# DCDCDC.net
KiCad netlist of a schematic drawn in EAGLE
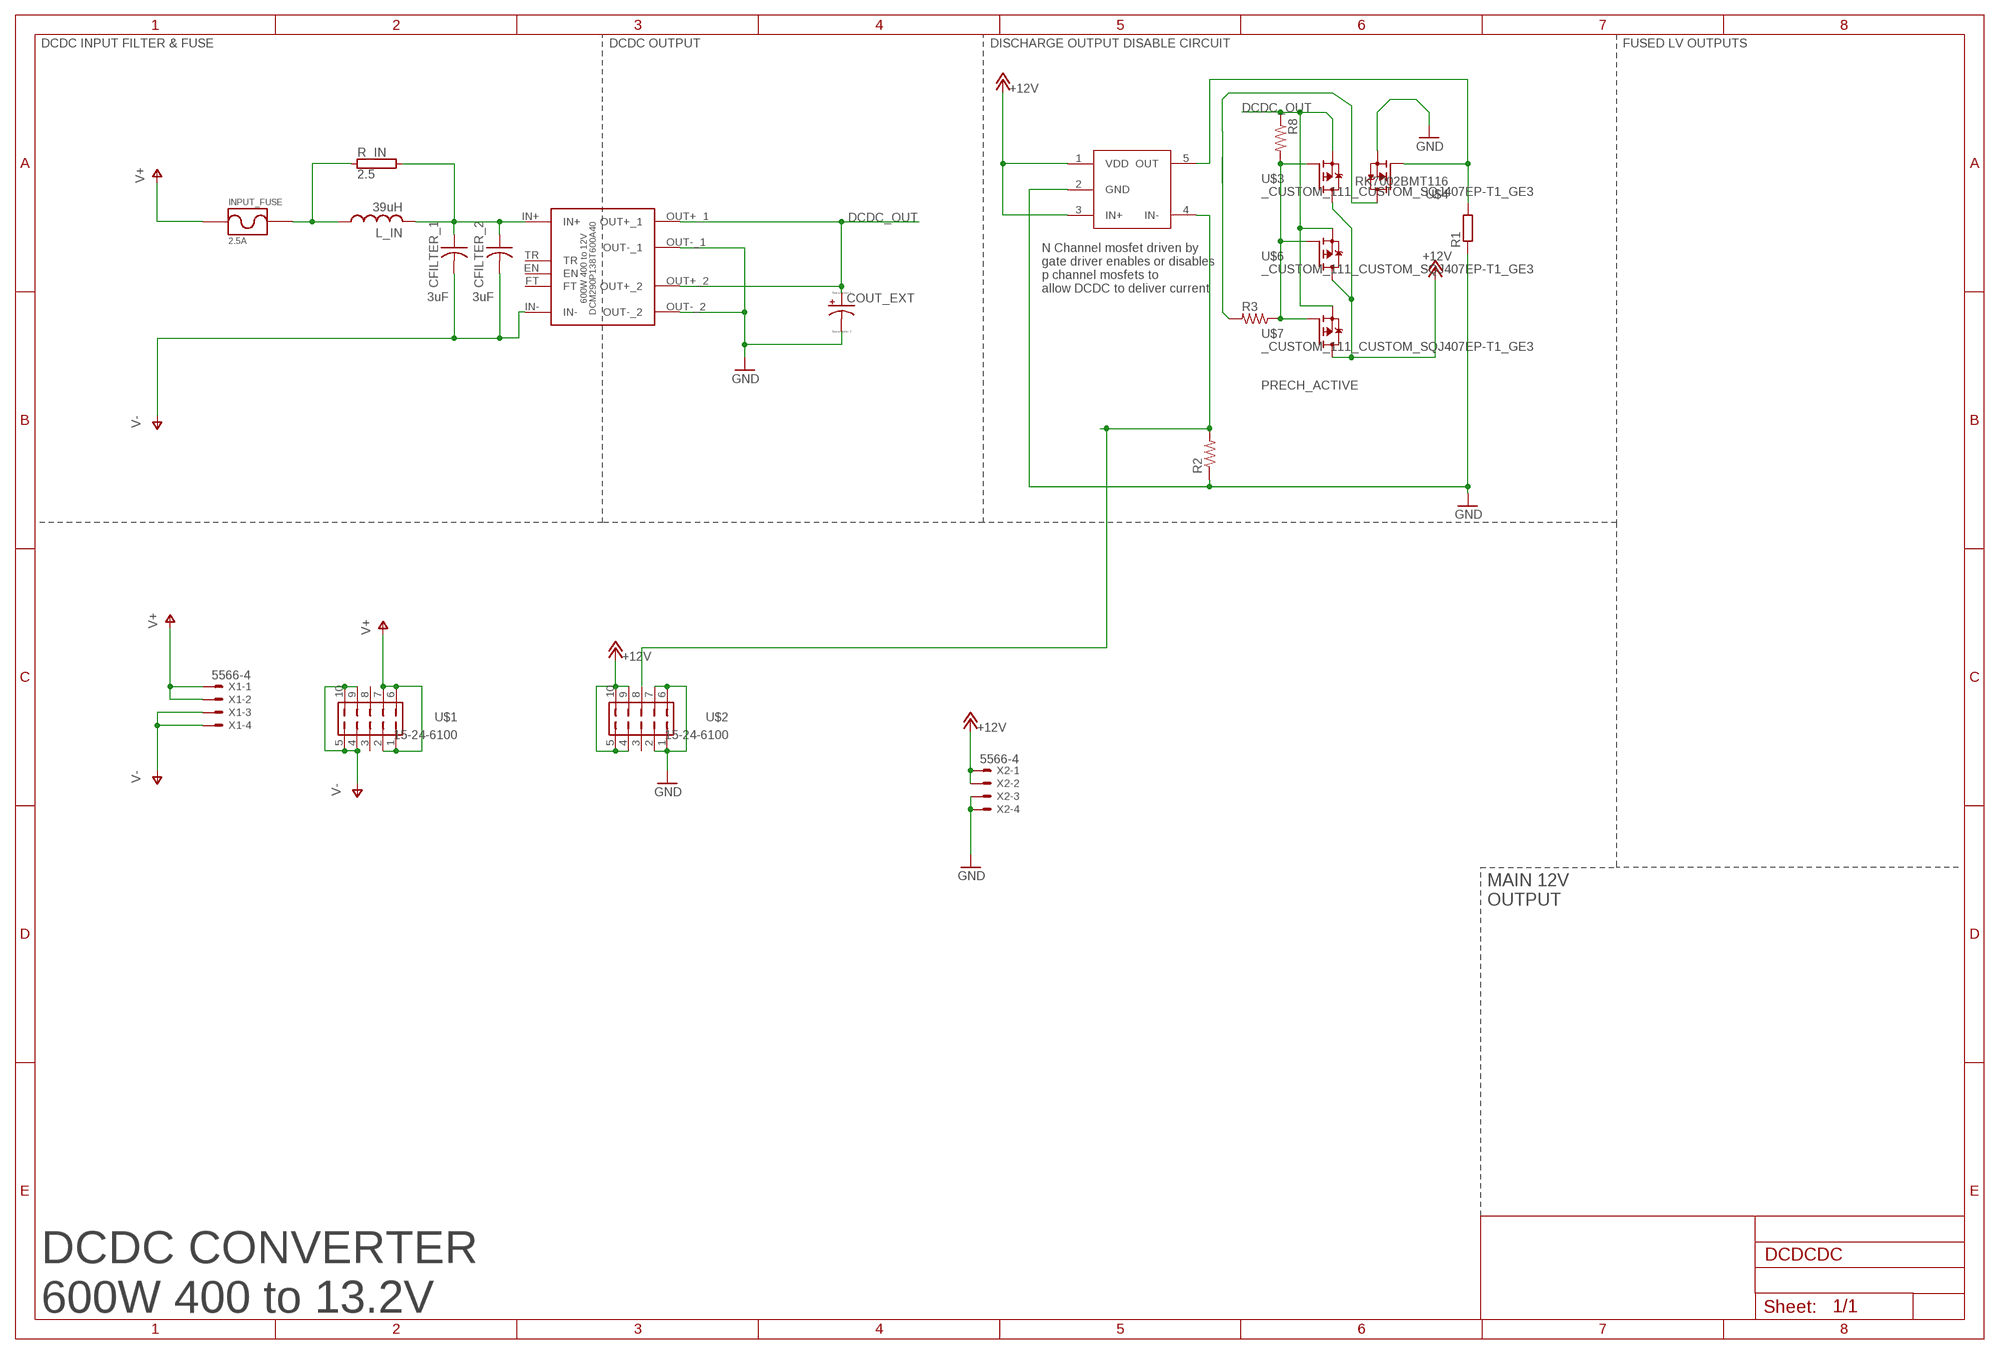
[diagram p0: schematic, sheet 1]

(export (version "E")
  (design (tool "Eeschema 10.0.6"))
  (components
    (comp (ref "CFILTER_1")
      (value "3uF")
      (footprint "eagle-import:CERALINK_FA3")
      (libsource (lib "eagle-import") (part "B58035U5305M062"))
    )
    (comp (ref "CFILTER_2")
      (value "3uF")
      (footprint "eagle-import:CERALINK_FA3")
      (libsource (lib "eagle-import") (part "B58035U5305M062"))
    )
    (comp (ref "COUT_EXT")
      (value "CPOL-USE7.5-16")
      (footprint "eagle-import:E7,5-16")
      (libsource (lib "eagle-import") (part "CPOL-USE7.5-16"))
    )
    (comp (ref "DCM290P138T600A40")
      (value "600W 400 to 12V")
      (footprint "eagle-import:VICOR_CHIP_HEATSINK")
      (libsource (lib "eagle-import") (part "VICOR_CHIP_WITH_HEATSINK"))
    )
    (comp (ref "INPUT_FUSE")
      (value "2.5A")
      (footprint "eagle-import:_CUSTOM_PARTS_LF_885")
      (libsource (lib "eagle-import") (part "_CUSTOM_PARTS_LF_885"))
    )
    (comp (ref "L_IN")
      (value "39uH")
      (footprint "eagle-import:L_1510_NONSTANDARD")
      (libsource (lib "eagle-import") (part "SRP1770TA-390M"))
    )
    (comp (ref "R1")
      (value "R-EU_R0805")
      (footprint "eagle-import:R0805")
      (libsource (lib "eagle-import") (part "R-EU_R0805"))
    )
    (comp (ref "R2")
      (value "R-US_R0805")
      (footprint "eagle-import:R0805")
      (libsource (lib "eagle-import") (part "R-US_R0805"))
    )
    (comp (ref "R3")
      (value "R-US_R0805")
      (footprint "eagle-import:R0805")
      (libsource (lib "eagle-import") (part "R-US_R0805"))
    )
    (comp (ref "R8")
      (value "R-US_R0805")
      (footprint "eagle-import:R0805")
      (libsource (lib "eagle-import") (part "R-US_R0805"))
    )
    (comp (ref "R_IN")
      (value "2.5")
      (footprint "eagle-import:TO-247-2V")
      (libsource (lib "eagle-import") (part "RMG100-V"))
    )
    (comp (ref "U$1")
      (value "15-24-6100")
      (footprint "eagle-import:15-24-6100")
      (libsource (lib "eagle-import") (part "15-24-6100"))
    )
    (comp (ref "U$2")
      (value "15-24-6100")
      (footprint "eagle-import:15-24-6100")
      (libsource (lib "eagle-import") (part "15-24-6100"))
    )
    (comp (ref "U$3")
      (value "_CUSTOM_111_CUSTOM_SQJ407EP-T1_GE3")
      (footprint "eagle-import:_CUSTOM_111_CUSTOM_TRANS_SIRA90DP-T1-GE3")
      (libsource (lib "eagle-import") (part "_CUSTOM_111_CUSTOM_SQJ407EP-T1_GE3"))
    )
    (comp (ref "U$4")
      (value "RK7002BMT116")
      (footprint "eagle-import:SOT23")
      (libsource (lib "eagle-import") (part "RK7002BMT116"))
    )
    (comp (ref "U$5")
      (value "UCC27511AQDBVRQ1")
      (footprint "eagle-import:SOT23-5L")
      (libsource (lib "eagle-import") (part "UCC27511AQDBVRQ1"))
    )
    (comp (ref "U$6")
      (value "_CUSTOM_111_CUSTOM_SQJ407EP-T1_GE3")
      (footprint "eagle-import:_CUSTOM_111_CUSTOM_TRANS_SIRA90DP-T1-GE3")
      (libsource (lib "eagle-import") (part "_CUSTOM_111_CUSTOM_SQJ407EP-T1_GE3"))
    )
    (comp (ref "U$7")
      (value "_CUSTOM_111_CUSTOM_SQJ407EP-T1_GE3")
      (footprint "eagle-import:_CUSTOM_111_CUSTOM_TRANS_SIRA90DP-T1-GE3")
      (libsource (lib "eagle-import") (part "_CUSTOM_111_CUSTOM_SQJ407EP-T1_GE3"))
    )
    (comp (ref "X1")
      (value "5566-4")
      (footprint "eagle-import:5566-4")
      (fields (field (name "MF") "MOLEX"))
      (libsource (lib "eagle-import") (part "5566-4"))
    )
    (comp (ref "X2")
      (value "5566-4")
      (footprint "eagle-import:5566-4")
      (fields (field (name "MF") "MOLEX"))
      (libsource (lib "eagle-import") (part "5566-4"))
    )
  )
  (nets
    (net (code "1") (name "+12V") (class "Default")
      (node (ref "U$2") (pin "10") (pinfunction "10_10") (pintype "passive"))
      (node (ref "U$2") (pin "4") (pinfunction "4_4") (pintype "passive"))
      (node (ref "U$2") (pin "5") (pinfunction "5_5") (pintype "passive"))
      (node (ref "U$2") (pin "9") (pinfunction "9_9") (pintype "passive"))
      (node (ref "U$3") (pin "5") (pinfunction "D_5") (pintype "passive"))
      (node (ref "U$5") (pin "1") (pinfunction "VDD_1") (pintype "bidirectional"))
      (node (ref "U$5") (pin "3") (pinfunction "IN+_3") (pintype "bidirectional"))
      (node (ref "U$6") (pin "5") (pinfunction "D_5") (pintype "passive"))
      (node (ref "U$7") (pin "5") (pinfunction "D_5") (pintype "passive"))
      (node (ref "X2") (pin "1") (pinfunction "S_1") (pintype "passive"))
      (node (ref "X2") (pin "2") (pinfunction "S_2") (pintype "passive"))
    )
    (net (code "2") (name "/DCDC_OUT") (class "Default")
      (node (ref "COUT_EXT") (pin "+") (pinfunction "+_+") (pintype "passive"))
      (node (ref "DCM290P138T600A40") (pin "OUT+_1") (pinfunction "OUT+_1_OUT+_1") (pintype "bidirectional"))
      (node (ref "DCM290P138T600A40") (pin "OUT+_2") (pinfunction "OUT+_2_OUT+_2") (pintype "bidirectional"))
      (node (ref "R8") (pin "1") (pinfunction "1_1") (pintype "passive"))
      (node (ref "U$3") (pin "1") (pinfunction "S_1") (pintype "passive"))
      (node (ref "U$3") (pin "2") (pinfunction "S_2") (pintype "passive"))
      (node (ref "U$3") (pin "3") (pinfunction "S_3") (pintype "passive"))
      (node (ref "U$6") (pin "1") (pinfunction "S_1") (pintype "passive"))
      (node (ref "U$6") (pin "2") (pinfunction "S_2") (pintype "passive"))
      (node (ref "U$6") (pin "3") (pinfunction "S_3") (pintype "passive"))
      (node (ref "U$7") (pin "1") (pinfunction "S_1") (pintype "passive"))
      (node (ref "U$7") (pin "2") (pinfunction "S_2") (pintype "passive"))
      (node (ref "U$7") (pin "3") (pinfunction "S_3") (pintype "passive"))
    )
    (net (code "3") (name "/PRECH_ACTIVE") (class "Default")
      (node (ref "R2") (pin "2") (pinfunction "2_2") (pintype "passive"))
      (node (ref "U$2") (pin "8") (pinfunction "8_8") (pintype "passive"))
      (node (ref "U$5") (pin "4") (pinfunction "IN-_4") (pintype "bidirectional"))
    )
    (net (code "4") (name "GND") (class "Default")
      (node (ref "COUT_EXT") (pin "-") (pinfunction "-_-") (pintype "passive"))
      (node (ref "DCM290P138T600A40") (pin "OUT-_1") (pinfunction "OUT-_1_OUT-_1") (pintype "bidirectional"))
      (node (ref "DCM290P138T600A40") (pin "OUT-_2") (pinfunction "OUT-_2_OUT-_2") (pintype "bidirectional"))
      (node (ref "R1") (pin "1") (pinfunction "1_1") (pintype "passive"))
      (node (ref "R2") (pin "1") (pinfunction "1_1") (pintype "passive"))
      (node (ref "U$2") (pin "1") (pinfunction "1_1") (pintype "passive"))
      (node (ref "U$2") (pin "2") (pinfunction "2_2") (pintype "passive"))
      (node (ref "U$2") (pin "6") (pinfunction "6_6") (pintype "passive"))
      (node (ref "U$2") (pin "7") (pinfunction "7_7") (pintype "passive"))
      (node (ref "U$4") (pin "2") (pinfunction "S_2") (pintype "passive"))
      (node (ref "U$5") (pin "2") (pinfunction "GND_2") (pintype "bidirectional"))
      (node (ref "X2") (pin "3") (pinfunction "S_3") (pintype "passive"))
      (node (ref "X2") (pin "4") (pinfunction "S_4") (pintype "passive"))
    )
    (net (code "5") (name "Net-(CFILTER_1-1)") (class "Default")
      (node (ref "CFILTER_1") (pin "P$1") (pinfunction "1_P$1") (pintype "passive"))
      (node (ref "CFILTER_2") (pin "P$1") (pinfunction "1_P$1") (pintype "passive"))
      (node (ref "DCM290P138T600A40") (pin "IN+") (pinfunction "IN+_IN+") (pintype "bidirectional"))
      (node (ref "L_IN") (pin "P$2") (pinfunction "2_P$2") (pintype "passive"))
      (node (ref "R_IN") (pin "2") (pinfunction "2_2") (pintype "passive"))
    )
    (net (code "6") (name "Net-(L_IN-1)") (class "Default")
      (node (ref "INPUT_FUSE") (pin "P$2") (pinfunction "P$2_P$2") (pintype "bidirectional"))
      (node (ref "L_IN") (pin "P$1") (pinfunction "1_P$1") (pintype "passive"))
      (node (ref "R_IN") (pin "1") (pinfunction "1_1") (pintype "passive"))
    )
    (net (code "7") (name "Net-(U$3-G)") (class "Default")
      (node (ref "R3") (pin "1") (pinfunction "1_1") (pintype "passive"))
      (node (ref "R8") (pin "2") (pinfunction "2_2") (pintype "passive"))
      (node (ref "U$3") (pin "4") (pinfunction "G_4") (pintype "passive"))
      (node (ref "U$6") (pin "4") (pinfunction "G_4") (pintype "passive"))
      (node (ref "U$7") (pin "4") (pinfunction "G_4") (pintype "passive"))
    )
    (net (code "8") (name "Net-(U$4-D)") (class "Default")
      (node (ref "R3") (pin "2") (pinfunction "2_2") (pintype "passive"))
      (node (ref "U$4") (pin "3") (pinfunction "D_3") (pintype "passive"))
    )
    (net (code "9") (name "Net-(U$4-G)") (class "Default")
      (node (ref "R1") (pin "2") (pinfunction "2_2") (pintype "passive"))
      (node (ref "U$4") (pin "1") (pinfunction "G_1") (pintype "passive"))
      (node (ref "U$5") (pin "5") (pinfunction "OUT_5") (pintype "bidirectional"))
    )
    (net (code "10") (name "V+") (class "Default")
      (node (ref "INPUT_FUSE") (pin "P$1") (pinfunction "P$1_P$1") (pintype "bidirectional"))
      (node (ref "U$1") (pin "1") (pinfunction "1_1") (pintype "passive"))
      (node (ref "U$1") (pin "2") (pinfunction "2_2") (pintype "passive"))
      (node (ref "U$1") (pin "6") (pinfunction "6_6") (pintype "passive"))
      (node (ref "U$1") (pin "7") (pinfunction "7_7") (pintype "passive"))
      (node (ref "X1") (pin "1") (pinfunction "S_1") (pintype "passive"))
      (node (ref "X1") (pin "2") (pinfunction "S_2") (pintype "passive"))
    )
    (net (code "11") (name "V-") (class "Default")
      (node (ref "CFILTER_1") (pin "P$2") (pinfunction "2_P$2") (pintype "passive"))
      (node (ref "CFILTER_2") (pin "P$2") (pinfunction "2_P$2") (pintype "passive"))
      (node (ref "DCM290P138T600A40") (pin "IN-") (pinfunction "IN-_IN-") (pintype "bidirectional"))
      (node (ref "U$1") (pin "10") (pinfunction "10_10") (pintype "passive"))
      (node (ref "U$1") (pin "4") (pinfunction "4_4") (pintype "passive"))
      (node (ref "U$1") (pin "5") (pinfunction "5_5") (pintype "passive"))
      (node (ref "U$1") (pin "9") (pinfunction "9_9") (pintype "passive"))
      (node (ref "X1") (pin "3") (pinfunction "S_3") (pintype "passive"))
      (node (ref "X1") (pin "4") (pinfunction "S_4") (pintype "passive"))
    )
    (net (code "12") (name "unconnected-(DCM290P138T600A40-PadEN)") (class "Default")
      (node (ref "DCM290P138T600A40") (pin "EN") (pinfunction "EN_EN") (pintype "bidirectional"))
    )
    (net (code "13") (name "unconnected-(DCM290P138T600A40-PadFT)") (class "Default")
      (node (ref "DCM290P138T600A40") (pin "FT") (pinfunction "FT_FT") (pintype "bidirectional"))
    )
    (net (code "14") (name "unconnected-(DCM290P138T600A40-PadTR)") (class "Default")
      (node (ref "DCM290P138T600A40") (pin "TR") (pinfunction "TR_TR") (pintype "bidirectional"))
    )
    (net (code "15") (name "unconnected-(U$1-Pad3)") (class "Default")
      (node (ref "U$1") (pin "3") (pinfunction "3_3") (pintype "passive"))
    )
    (net (code "16") (name "unconnected-(U$1-Pad8)") (class "Default")
      (node (ref "U$1") (pin "8") (pinfunction "8_8") (pintype "passive"))
    )
    (net (code "17") (name "unconnected-(U$2-Pad3)") (class "Default")
      (node (ref "U$2") (pin "3") (pinfunction "3_3") (pintype "passive"))
    )
  )
)
